# Control.net
KiCad netlist of a schematic drawn in Altium Designer
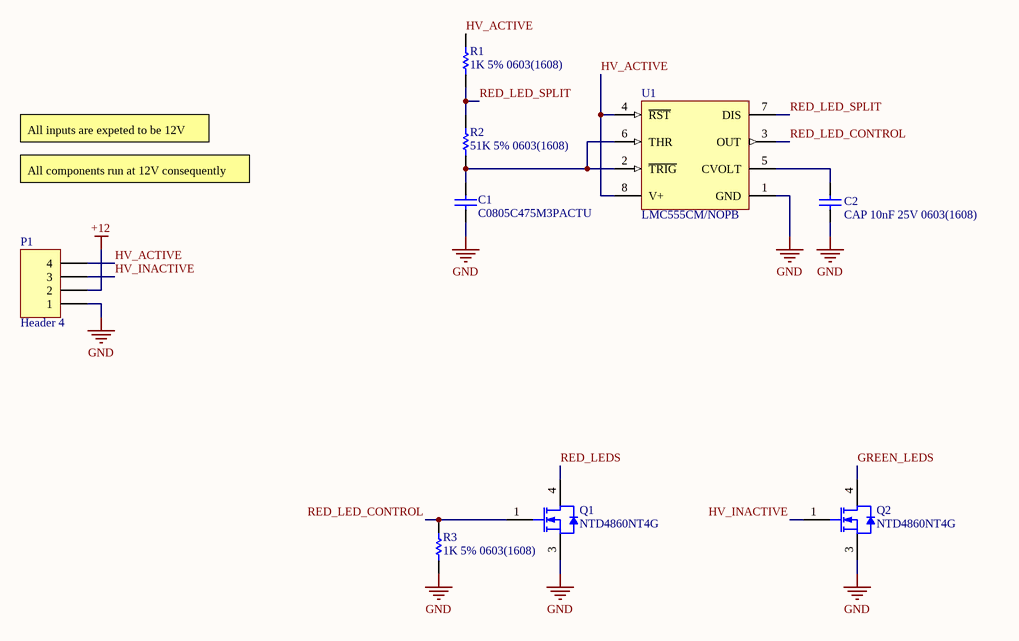
[diagram p0: Control.SchDoc]

(export (version "E")
  (design (tool "Eeschema 10.0.6"))
  (components
    (comp (ref "C1")
      (value "C0805C475M3PACTU")
      (footprint "CAPC2013X145X50NL20T25")
      (fields (field (name "MANUFACTURER") "Kemet"))
      (libsource (lib "Altium Content Vault") (part "CAP"))
    )
    (comp (ref "C2")
      (value "CAP 10nF 25V 0603(1608)")
      (footprint "CAPC0603(1608)100_M")
      (description "CAP 10nF 25V ±5% 0603 (1608 Metric) Thickness 1mm SMD")
      (fields (field (name "TOLERANCE") "Â±5%"))
      (libsource (lib "Altium Content Vault") (part "CAP"))
    )
    (comp (ref "P1")
      (value "Header 4")
      (footprint "HDR1X4")
      (description "Header, 4-Pin")
      (fields (field (name "PUBLISHER") "Altium Limited"))
      (libsource (lib "Miscellaneous Connectors") (part "Header 4"))
    )
    (comp (ref "Q1")
      (value "NTD4860NT4G")
      (footprint "ONSC-DPAK-3-369AA-01_V")
      (description "Power MOSFET, 25 V, 65 A, Single N-Channel, 3-Pin DPAK, Pb-Free, Tape and Reel")
      (fields (field (name "MANUFACTURER") "On Semiconductor"))
      (libsource (lib "Altium Content Vault") (part "ONSC-NMOS-G1S3D4-3_B"))
    )
    (comp (ref "Q2")
      (value "NTD4860NT4G")
      (footprint "ONSC-DPAK-3-369AA-01_V")
      (description "Power MOSFET, 25 V, 65 A, Single N-Channel, 3-Pin DPAK, Pb-Free, Tape and Reel")
      (fields (field (name "MANUFACTURER") "On Semiconductor"))
      (libsource (lib "Altium Content Vault") (part "ONSC-NMOS-G1S3D4-3_B"))
    )
    (comp (ref "R1")
      (value "1K 5% 0603(1608)")
      (footprint "RESC0603(1608)_L")
      (description "1K 0.1W 5% 0603 (1608 Metric)  SMD")
      (fields (field (name "TOLERANCE") "5 %") (field (name "POWER") "0.1 W"))
      (libsource (lib "Altium Content Vault") (part "RES"))
    )
    (comp (ref "R2")
      (value "51K 5% 0603(1608)")
      (footprint "RESC0603(1608)_M")
      (description "51K 0.1W 5% 0603 (1608 Metric)  SMD")
      (fields (field (name "POWER") "0.1 W") (field (name "TOLERANCE") "5 %"))
      (libsource (lib "Altium Content Vault") (part "RES"))
    )
    (comp (ref "R3")
      (value "1K 5% 0603(1608)")
      (footprint "RESC0603(1608)_L")
      (description "1K 0.1W 5% 0603 (1608 Metric)  SMD")
      (fields (field (name "TOLERANCE") "5 %") (field (name "POWER") "0.1 W"))
      (libsource (lib "Altium Content Vault") (part "RES"))
    )
    (comp (ref "U1")
      (value "LMC555CM/NOPB")
      (footprint "D0008A_L")
      (description "CMOS Timer, 8-pin Narrow SOIC, Pb-Free")
      (fields (field (name "MANUFACTURER") "Texas Instruments"))
      (libsource (lib "Altium Content Vault") (part "AN-TIMER-LMC555-8"))
    )
  )
  (nets
    (net (code "1") (name "+12") (class "Default")
      (node (ref "P1") (pin "2") (pinfunction "2_2") (pintype "passive"))
    )
    (net (code "2") (name "/GREEN_LEDS") (class "Default")
      (node (ref "Q2") (pin "4") (pinfunction "D_4") (pintype "passive"))
    )
    (net (code "3") (name "/HV_ACTIVE") (class "Default")
      (node (ref "P1") (pin "4") (pinfunction "4_4") (pintype "passive"))
      (node (ref "R1") (pin "2") (pinfunction "2_2") (pintype "passive"))
      (node (ref "U1") (pin "4") (pinfunction "~{RST}_4") (pintype "input"))
      (node (ref "U1") (pin "8") (pinfunction "V+_8") (pintype "power_in"))
    )
    (net (code "4") (name "/HV_INACTIVE") (class "Default")
      (node (ref "P1") (pin "3") (pinfunction "3_3") (pintype "passive"))
      (node (ref "Q2") (pin "1") (pinfunction "G_1") (pintype "passive"))
    )
    (net (code "5") (name "/RED_LEDS") (class "Default")
      (node (ref "Q1") (pin "4") (pinfunction "D_4") (pintype "passive"))
    )
    (net (code "6") (name "/RED_LED_CONTROL") (class "Default")
      (node (ref "Q1") (pin "1") (pinfunction "G_1") (pintype "passive"))
      (node (ref "R3") (pin "2") (pinfunction "2_2") (pintype "passive"))
      (node (ref "U1") (pin "3") (pinfunction "OUT_3") (pintype "output"))
    )
    (net (code "7") (name "/RED_LED_SPLIT") (class "Default")
      (node (ref "R1") (pin "1") (pinfunction "1_1") (pintype "passive"))
      (node (ref "R2") (pin "2") (pinfunction "2_2") (pintype "passive"))
      (node (ref "U1") (pin "7") (pinfunction "DIS_7") (pintype "open_collector"))
    )
    (net (code "8") (name "GND") (class "Default")
      (node (ref "C1") (pin "1") (pinfunction "1_1") (pintype "passive"))
      (node (ref "C2") (pin "1") (pinfunction "1_1") (pintype "passive"))
      (node (ref "P1") (pin "1") (pinfunction "1_1") (pintype "passive"))
      (node (ref "Q1") (pin "3") (pinfunction "S_3") (pintype "passive"))
      (node (ref "Q2") (pin "3") (pinfunction "S_3") (pintype "passive"))
      (node (ref "R3") (pin "1") (pinfunction "1_1") (pintype "passive"))
      (node (ref "U1") (pin "1") (pinfunction "GND_1") (pintype "power_in"))
    )
    (net (code "9") (name "Net-(U1-CVOLT)") (class "Default")
      (node (ref "C2") (pin "2") (pinfunction "2_2") (pintype "passive"))
      (node (ref "U1") (pin "5") (pinfunction "CVOLT_5") (pintype "passive"))
    )
    (net (code "10") (name "Net-(U1-THR)") (class "Default")
      (node (ref "C1") (pin "2") (pinfunction "2_2") (pintype "passive"))
      (node (ref "R2") (pin "1") (pinfunction "1_1") (pintype "passive"))
      (node (ref "U1") (pin "2") (pinfunction "~{TRIG}_2") (pintype "input"))
      (node (ref "U1") (pin "6") (pinfunction "THR_6") (pintype "input"))
    )
  )
)
